# GucciMain.net
KiCad netlist of a schematic drawn in EAGLE
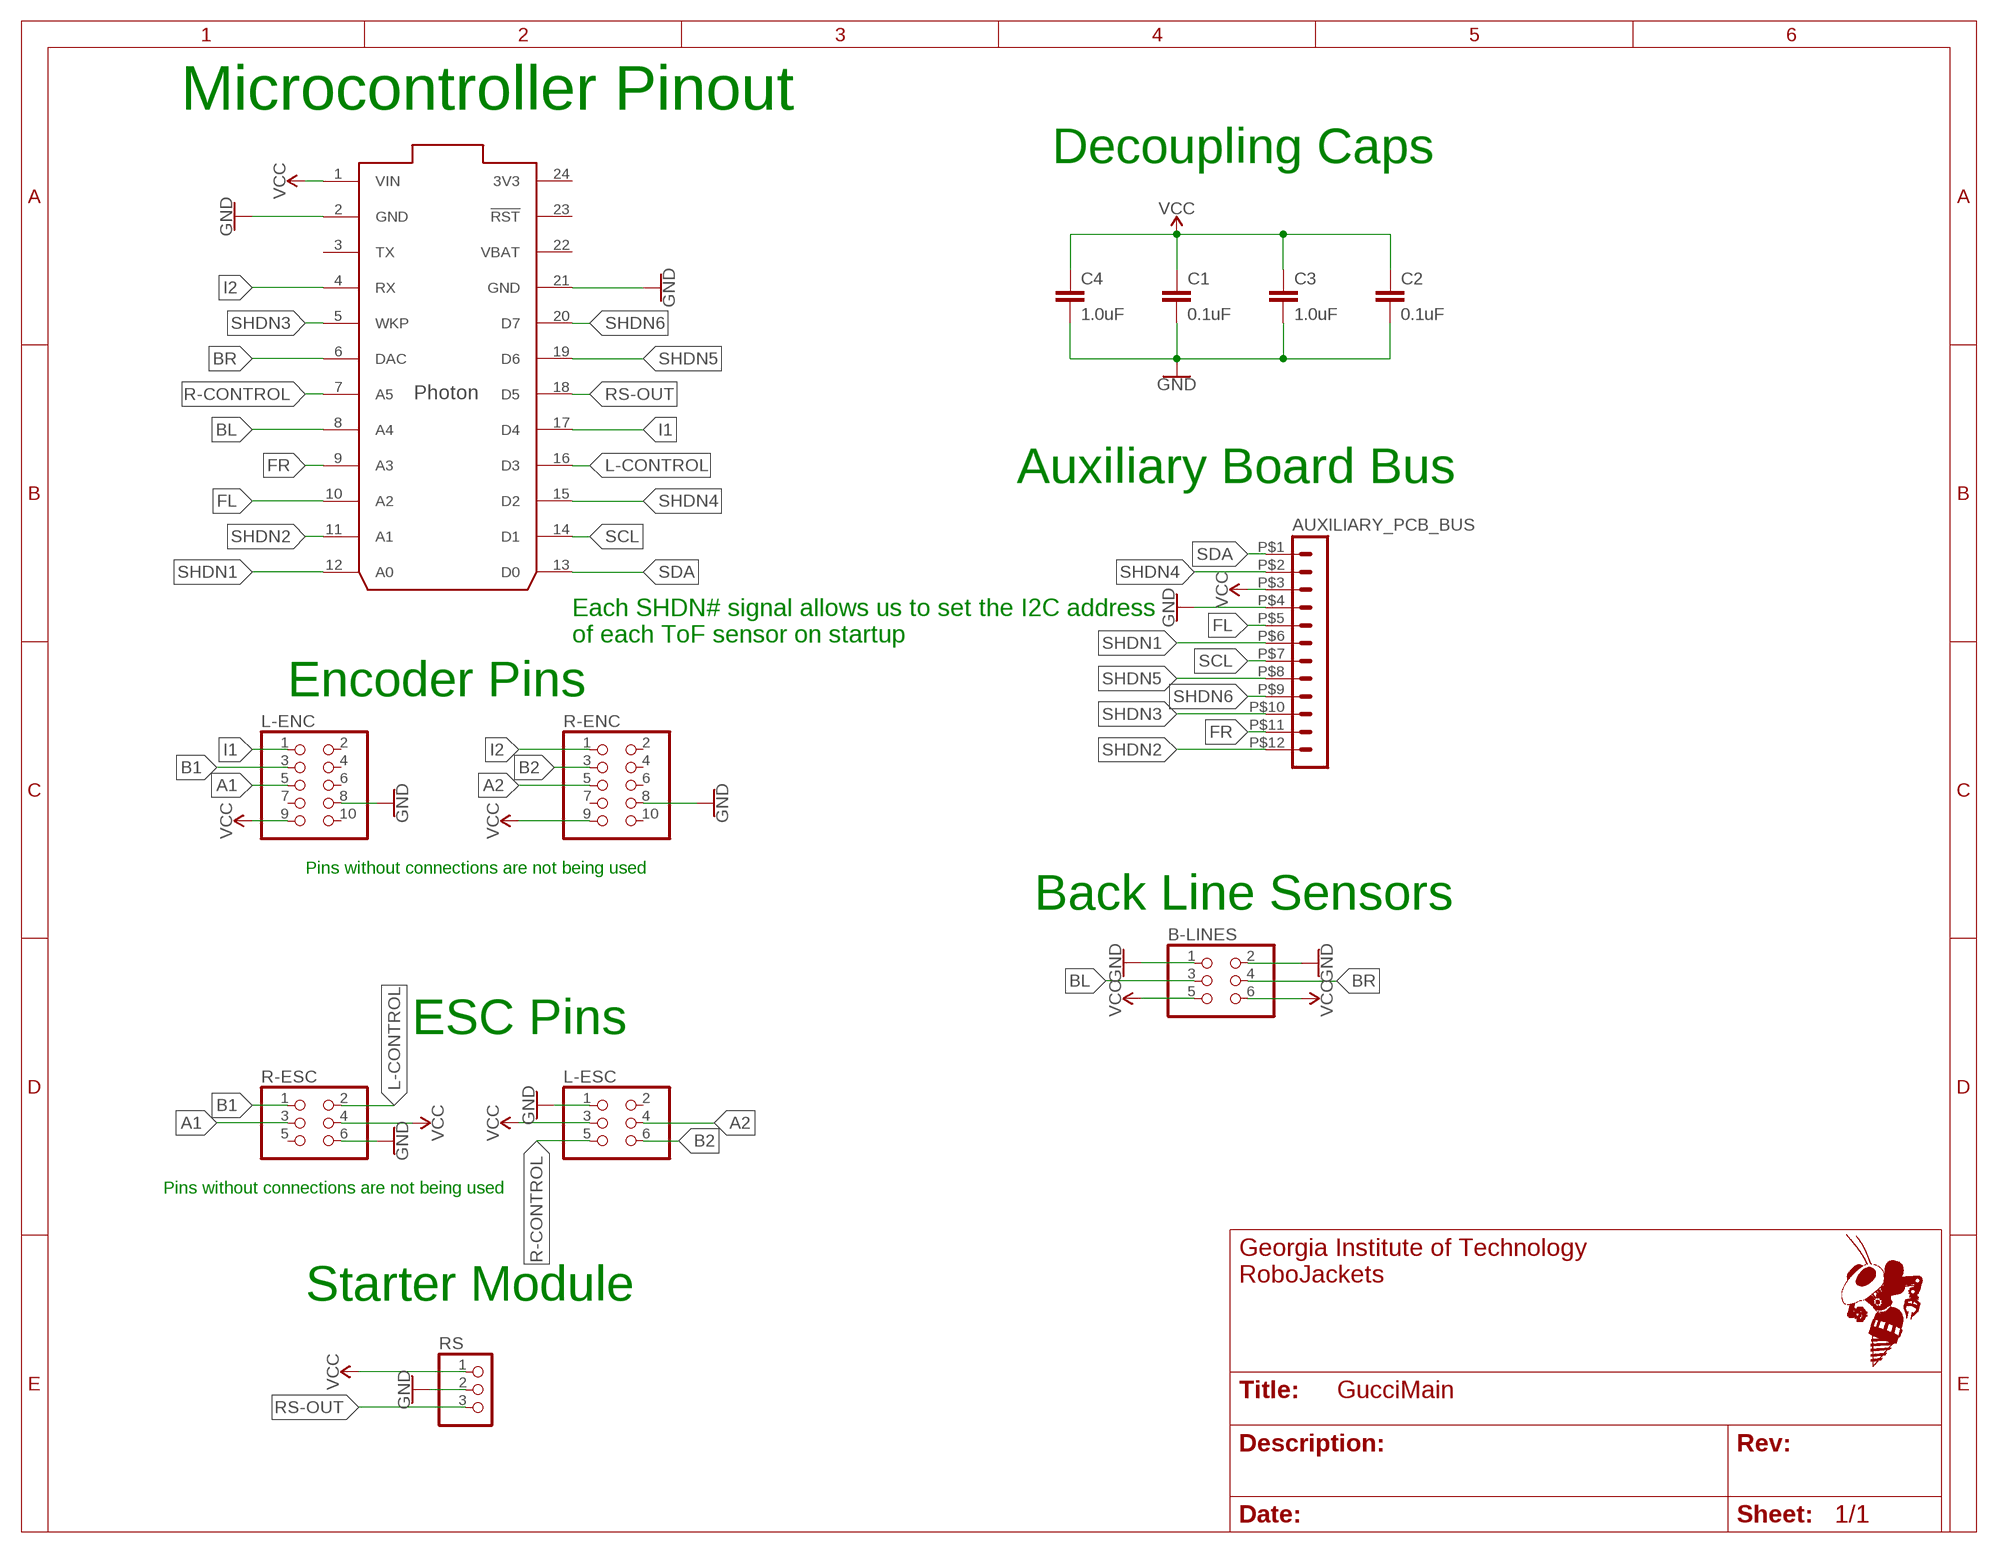
[diagram p0: schematic, sheet 1]

(export (version "E")
  (design (tool "Eeschema 10.0.6"))
  (components
    (comp (ref "AUXILIARY_PCB_BUS")
      (value "HEADER_POS12_43045-1212")
      (footprint "eagle-import:43045-1212")
      (libsource (lib "eagle-import") (part "HEADER_POS12_?43045-1212"))
    )
    (comp (ref "B-LINES")
      (value "PINHD-2X3/90")
      (footprint "eagle-import:2X03_90")
      (libsource (lib "eagle-import") (part "PINHD-2X3/90"))
    )
    (comp (ref "C1")
      (value "0.1uF")
      (footprint "eagle-import:0603")
      (libsource (lib "eagle-import") (part "0.1UF-0603-100V-10%"))
    )
    (comp (ref "C2")
      (value "0.1uF")
      (footprint "eagle-import:0603")
      (libsource (lib "eagle-import") (part "0.1UF-0603-100V-10%"))
    )
    (comp (ref "C3")
      (value "1.0uF")
      (footprint "eagle-import:0603")
      (libsource (lib "eagle-import") (part "1.0UF-0603-16V-10%"))
    )
    (comp (ref "C4")
      (value "1.0uF")
      (footprint "eagle-import:0603")
      (libsource (lib "eagle-import") (part "1.0UF-0603-16V-10%"))
    )
    (comp (ref "L-ENC")
      (value "PINHD-2X5/90")
      (footprint "eagle-import:2X05_90")
      (libsource (lib "eagle-import") (part "PINHD-2X5/90"))
    )
    (comp (ref "L-ESC")
      (value "PINHD-2X3")
      (footprint "eagle-import:2X03")
      (libsource (lib "eagle-import") (part "PINHD-2X3"))
    )
    (comp (ref "PHOTON")
      (value "PHOTON")
      (footprint "eagle-import:PHOTON")
      (libsource (lib "eagle-import") (part "PHOTON_WITH_HEADERS"))
    )
    (comp (ref "R-ENC")
      (value "PINHD-2X5/90")
      (footprint "eagle-import:2X05_90")
      (libsource (lib "eagle-import") (part "PINHD-2X5/90"))
    )
    (comp (ref "R-ESC")
      (value "PINHD-2X3")
      (footprint "eagle-import:2X03")
      (libsource (lib "eagle-import") (part "PINHD-2X3"))
    )
    (comp (ref "RS")
      (value "PINHD-1X3")
      (footprint "eagle-import:1X03")
      (libsource (lib "eagle-import") (part "PINHD-1X3"))
    )
  )
  (nets
    (net (code "1") (name "/3V3") (class "Default")
      (node (ref "PHOTON") (pin "24") (pinfunction "3V3_24") (pintype "power_in"))
    )
    (net (code "2") (name "/VBAT") (class "Default")
      (node (ref "PHOTON") (pin "22") (pinfunction "VBAT_22") (pintype "power_in"))
    )
    (net (code "3") (name "A1") (class "Default")
      (node (ref "L-ENC") (pin "5") (pinfunction "5_5") (pintype "passive"))
      (node (ref "R-ESC") (pin "3") (pinfunction "3_3") (pintype "passive"))
    )
    (net (code "4") (name "A2") (class "Default")
      (node (ref "L-ESC") (pin "4") (pinfunction "4_4") (pintype "passive"))
      (node (ref "R-ENC") (pin "5") (pinfunction "5_5") (pintype "passive"))
    )
    (net (code "5") (name "B1") (class "Default")
      (node (ref "L-ENC") (pin "3") (pinfunction "3_3") (pintype "passive"))
      (node (ref "R-ESC") (pin "1") (pinfunction "1_1") (pintype "passive"))
    )
    (net (code "6") (name "B2") (class "Default")
      (node (ref "L-ESC") (pin "6") (pinfunction "6_6") (pintype "passive"))
      (node (ref "R-ENC") (pin "3") (pinfunction "3_3") (pintype "passive"))
    )
    (net (code "7") (name "BL") (class "Default")
      (node (ref "B-LINES") (pin "3") (pinfunction "3_3") (pintype "passive"))
      (node (ref "PHOTON") (pin "8") (pinfunction "A4_8") (pintype "bidirectional"))
    )
    (net (code "8") (name "BR") (class "Default")
      (node (ref "B-LINES") (pin "4") (pinfunction "4_4") (pintype "passive"))
      (node (ref "PHOTON") (pin "6") (pinfunction "DAC_6") (pintype "bidirectional"))
    )
    (net (code "9") (name "FL") (class "Default")
      (node (ref "AUXILIARY_PCB_BUS") (pin "P$5") (pinfunction "5_P$5") (pintype "passive"))
      (node (ref "PHOTON") (pin "10") (pinfunction "A2_10") (pintype "bidirectional"))
    )
    (net (code "10") (name "FR") (class "Default")
      (node (ref "AUXILIARY_PCB_BUS") (pin "P$11") (pinfunction "11_P$11") (pintype "passive"))
      (node (ref "PHOTON") (pin "9") (pinfunction "A3_9") (pintype "bidirectional"))
    )
    (net (code "11") (name "GND") (class "Default")
      (node (ref "AUXILIARY_PCB_BUS") (pin "P$4") (pinfunction "4_P$4") (pintype "passive"))
      (node (ref "B-LINES") (pin "1") (pinfunction "1_1") (pintype "passive"))
      (node (ref "B-LINES") (pin "2") (pinfunction "2_2") (pintype "passive"))
      (node (ref "C1") (pin "2") (pinfunction "2_2") (pintype "passive"))
      (node (ref "C2") (pin "2") (pinfunction "2_2") (pintype "passive"))
      (node (ref "C3") (pin "2") (pinfunction "2_2") (pintype "passive"))
      (node (ref "C4") (pin "2") (pinfunction "2_2") (pintype "passive"))
      (node (ref "L-ENC") (pin "8") (pinfunction "8_8") (pintype "passive"))
      (node (ref "L-ESC") (pin "1") (pinfunction "1_1") (pintype "passive"))
      (node (ref "PHOTON") (pin "2") (pinfunction "GND_2") (pintype "power_in"))
      (node (ref "PHOTON") (pin "21") (pinfunction "GND_21") (pintype "power_in"))
      (node (ref "R-ENC") (pin "8") (pinfunction "8_8") (pintype "passive"))
      (node (ref "R-ESC") (pin "6") (pinfunction "6_6") (pintype "passive"))
      (node (ref "RS") (pin "2") (pinfunction "2_2") (pintype "passive"))
    )
    (net (code "12") (name "I1") (class "Default")
      (node (ref "L-ENC") (pin "1") (pinfunction "1_1") (pintype "passive"))
      (node (ref "PHOTON") (pin "17") (pinfunction "D4_17") (pintype "bidirectional"))
    )
    (net (code "13") (name "I2") (class "Default")
      (node (ref "PHOTON") (pin "4") (pinfunction "RX_4") (pintype "bidirectional"))
      (node (ref "R-ENC") (pin "1") (pinfunction "1_1") (pintype "passive"))
    )
    (net (code "14") (name "L-CONTROL") (class "Default")
      (node (ref "PHOTON") (pin "16") (pinfunction "D3_16") (pintype "bidirectional"))
      (node (ref "R-ESC") (pin "2") (pinfunction "2_2") (pintype "passive"))
    )
    (net (code "15") (name "R-CONTROL") (class "Default")
      (node (ref "L-ESC") (pin "5") (pinfunction "5_5") (pintype "passive"))
      (node (ref "PHOTON") (pin "7") (pinfunction "A5_7") (pintype "bidirectional"))
    )
    (net (code "16") (name "RS-OUT") (class "Default")
      (node (ref "PHOTON") (pin "18") (pinfunction "D5_18") (pintype "bidirectional"))
      (node (ref "RS") (pin "3") (pinfunction "3_3") (pintype "passive"))
    )
    (net (code "17") (name "SCL") (class "Default")
      (node (ref "AUXILIARY_PCB_BUS") (pin "P$7") (pinfunction "7_P$7") (pintype "passive"))
      (node (ref "PHOTON") (pin "14") (pinfunction "D1_14") (pintype "bidirectional"))
    )
    (net (code "18") (name "SDA") (class "Default")
      (node (ref "AUXILIARY_PCB_BUS") (pin "P$1") (pinfunction "1_P$1") (pintype "passive"))
      (node (ref "PHOTON") (pin "13") (pinfunction "D0_13") (pintype "bidirectional"))
    )
    (net (code "19") (name "SHDN1") (class "Default")
      (node (ref "AUXILIARY_PCB_BUS") (pin "P$6") (pinfunction "6_P$6") (pintype "passive"))
      (node (ref "PHOTON") (pin "12") (pinfunction "A0_12") (pintype "bidirectional"))
    )
    (net (code "20") (name "SHDN2") (class "Default")
      (node (ref "AUXILIARY_PCB_BUS") (pin "P$12") (pinfunction "12_P$12") (pintype "passive"))
      (node (ref "PHOTON") (pin "11") (pinfunction "A1_11") (pintype "bidirectional"))
    )
    (net (code "21") (name "SHDN3") (class "Default")
      (node (ref "AUXILIARY_PCB_BUS") (pin "P$10") (pinfunction "10_P$10") (pintype "passive"))
      (node (ref "PHOTON") (pin "5") (pinfunction "WKP_5") (pintype "bidirectional"))
    )
    (net (code "22") (name "SHDN4") (class "Default")
      (node (ref "AUXILIARY_PCB_BUS") (pin "P$2") (pinfunction "2_P$2") (pintype "passive"))
      (node (ref "PHOTON") (pin "15") (pinfunction "D2_15") (pintype "bidirectional"))
    )
    (net (code "23") (name "SHDN5") (class "Default")
      (node (ref "AUXILIARY_PCB_BUS") (pin "P$8") (pinfunction "8_P$8") (pintype "passive"))
      (node (ref "PHOTON") (pin "19") (pinfunction "D6_19") (pintype "bidirectional"))
    )
    (net (code "24") (name "SHDN6") (class "Default")
      (node (ref "AUXILIARY_PCB_BUS") (pin "P$9") (pinfunction "9_P$9") (pintype "passive"))
      (node (ref "PHOTON") (pin "20") (pinfunction "D7_20") (pintype "bidirectional"))
    )
    (net (code "25") (name "VCC") (class "Default")
      (node (ref "AUXILIARY_PCB_BUS") (pin "P$3") (pinfunction "3_P$3") (pintype "passive"))
      (node (ref "B-LINES") (pin "5") (pinfunction "5_5") (pintype "passive"))
      (node (ref "B-LINES") (pin "6") (pinfunction "6_6") (pintype "passive"))
      (node (ref "C1") (pin "1") (pinfunction "1_1") (pintype "passive"))
      (node (ref "C2") (pin "1") (pinfunction "1_1") (pintype "passive"))
      (node (ref "C3") (pin "1") (pinfunction "1_1") (pintype "passive"))
      (node (ref "C4") (pin "1") (pinfunction "1_1") (pintype "passive"))
      (node (ref "L-ENC") (pin "9") (pinfunction "9_9") (pintype "passive"))
      (node (ref "L-ESC") (pin "3") (pinfunction "3_3") (pintype "passive"))
      (node (ref "PHOTON") (pin "1") (pinfunction "VIN_1") (pintype "power_in"))
      (node (ref "R-ENC") (pin "9") (pinfunction "9_9") (pintype "passive"))
      (node (ref "R-ESC") (pin "4") (pinfunction "4_4") (pintype "passive"))
      (node (ref "RS") (pin "1") (pinfunction "1_1") (pintype "passive"))
    )
    (net (code "26") (name "unconnected-(L-ENC-Pad2)") (class "Default")
      (node (ref "L-ENC") (pin "2") (pinfunction "2_2") (pintype "passive"))
    )
    (net (code "27") (name "unconnected-(L-ENC-Pad4)") (class "Default")
      (node (ref "L-ENC") (pin "4") (pinfunction "4_4") (pintype "passive"))
    )
    (net (code "28") (name "unconnected-(L-ENC-Pad6)") (class "Default")
      (node (ref "L-ENC") (pin "6") (pinfunction "6_6") (pintype "passive"))
    )
    (net (code "29") (name "unconnected-(L-ENC-Pad7)") (class "Default")
      (node (ref "L-ENC") (pin "7") (pinfunction "7_7") (pintype "passive"))
    )
    (net (code "30") (name "unconnected-(L-ENC-Pad10)") (class "Default")
      (node (ref "L-ENC") (pin "10") (pinfunction "10_10") (pintype "passive"))
    )
    (net (code "31") (name "unconnected-(L-ESC-Pad2)") (class "Default")
      (node (ref "L-ESC") (pin "2") (pinfunction "2_2") (pintype "passive"))
    )
    (net (code "32") (name "unconnected-(PHOTON-TX-Pad3)") (class "Default")
      (node (ref "PHOTON") (pin "3") (pinfunction "TX_3") (pintype "bidirectional"))
    )
    (net (code "33") (name "unconnected-(PHOTON-~{RST}-Pad23)") (class "Default")
      (node (ref "PHOTON") (pin "23") (pinfunction "~{RST}_23") (pintype "bidirectional"))
    )
    (net (code "34") (name "unconnected-(R-ENC-Pad2)") (class "Default")
      (node (ref "R-ENC") (pin "2") (pinfunction "2_2") (pintype "passive"))
    )
    (net (code "35") (name "unconnected-(R-ENC-Pad4)") (class "Default")
      (node (ref "R-ENC") (pin "4") (pinfunction "4_4") (pintype "passive"))
    )
    (net (code "36") (name "unconnected-(R-ENC-Pad6)") (class "Default")
      (node (ref "R-ENC") (pin "6") (pinfunction "6_6") (pintype "passive"))
    )
    (net (code "37") (name "unconnected-(R-ENC-Pad7)") (class "Default")
      (node (ref "R-ENC") (pin "7") (pinfunction "7_7") (pintype "passive"))
    )
    (net (code "38") (name "unconnected-(R-ENC-Pad10)") (class "Default")
      (node (ref "R-ENC") (pin "10") (pinfunction "10_10") (pintype "passive"))
    )
    (net (code "39") (name "unconnected-(R-ESC-Pad5)") (class "Default")
      (node (ref "R-ESC") (pin "5") (pinfunction "5_5") (pintype "passive"))
    )
  )
)
